# ADC_Chip.net
KiCad netlist of a schematic drawn in Altium Designer
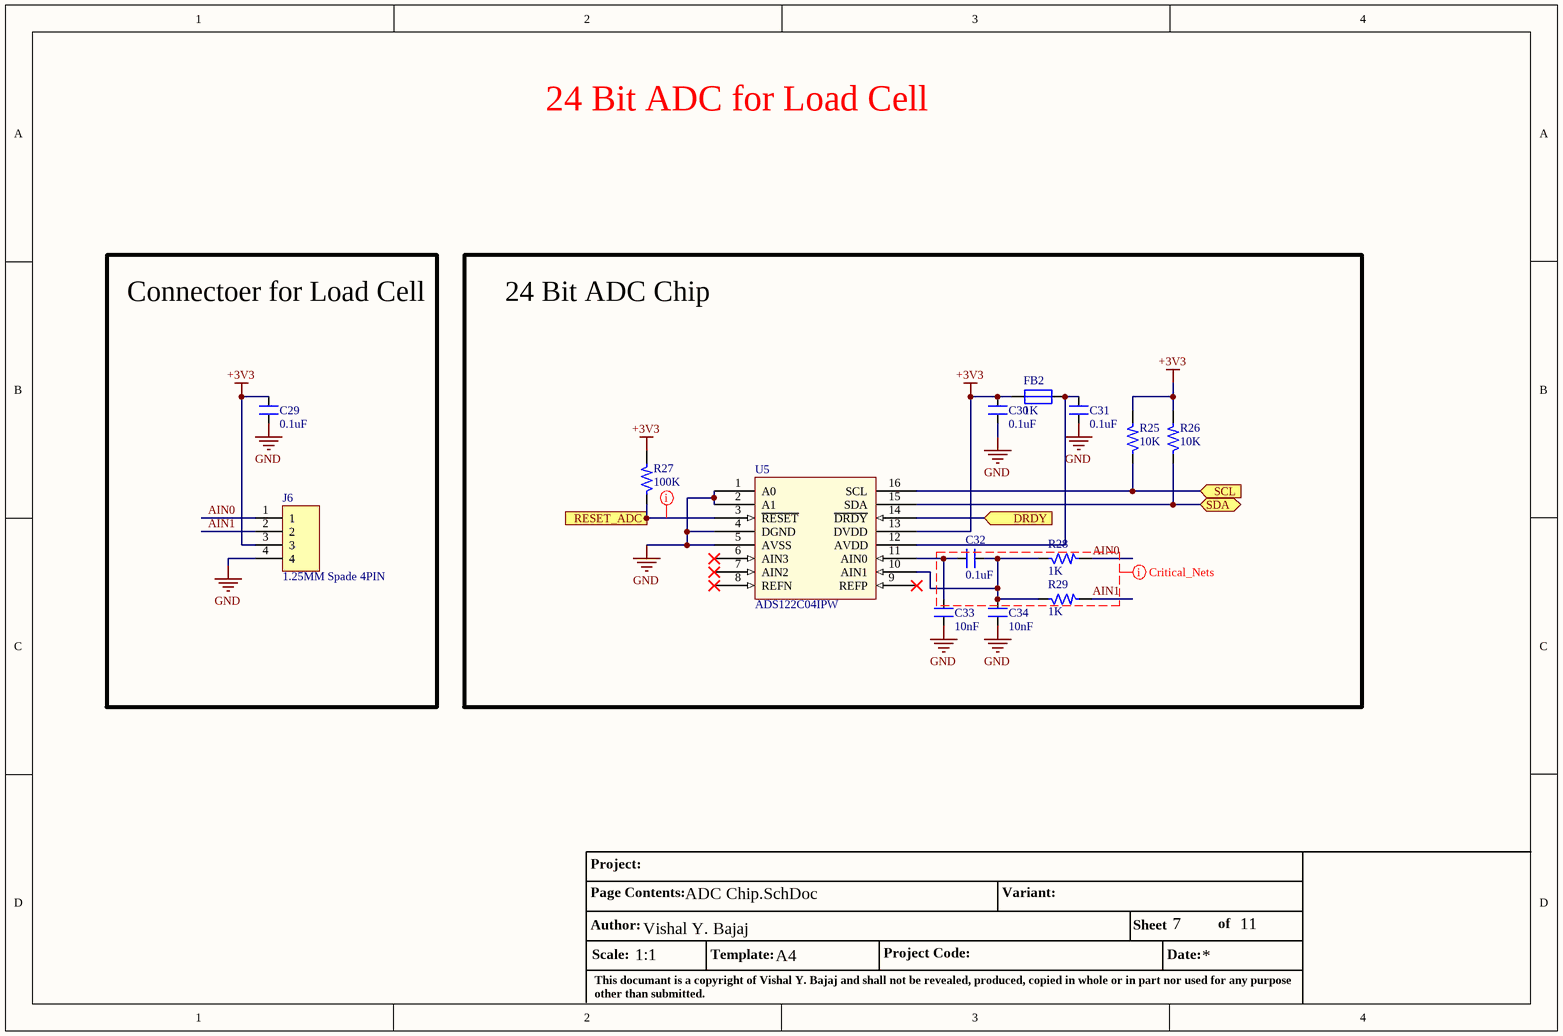
[diagram p0: ADC Chip.SchDoc]

(export (version "E")
  (design (tool "Eeschema 10.0.6"))
  (components
    (comp (ref "C29")
      (value "0.1uF")
      (footprint "CAP_0805")
      (description "0.1µF ±10% 50V Ceramic Capacitor X7R 0805 (2012 Metric)")
      (fields
        (field (name "MANUFACTURER") "Samsung")
        (field (name "MANUFACTURER PART NUMBER") "CL21B104KBCNNNC")
      )
      (libsource (lib "ESTEEMPCBLIB") (part "CAP_0.1uF-50V-10%-0805"))
    )
    (comp (ref "C30")
      (value "0.1uF")
      (footprint "CAP_0805")
      (description "0.1µF ±10% 50V Ceramic Capacitor X7R 0805 (2012 Metric)")
      (fields
        (field (name "MANUFACTURER") "Samsung")
        (field (name "MANUFACTURER PART NUMBER") "CL21B104KBCNNNC")
      )
      (libsource (lib "ESTEEMPCBLIB") (part "CAP_0.1uF-50V-10%-0805"))
    )
    (comp (ref "C31")
      (value "0.1uF")
      (footprint "CAP_0805")
      (description "0.1µF ±10% 50V Ceramic Capacitor X7R 0805 (2012 Metric)")
      (fields
        (field (name "MANUFACTURER") "Samsung")
        (field (name "MANUFACTURER PART NUMBER") "CL21B104KBCNNNC")
      )
      (libsource (lib "ESTEEMPCBLIB") (part "CAP_0.1uF-50V-10%-0805"))
    )
    (comp (ref "C32")
      (value "0.1uF")
      (footprint "CAP_0805")
      (description "0.1µF ±10% 50V Ceramic Capacitor X7R 0805 (2012 Metric)")
      (fields
        (field (name "MANUFACTURER") "Samsung")
        (field (name "MANUFACTURER PART NUMBER") "CL21B104KBCNNNC")
      )
      (libsource (lib "ESTEEMPCBLIB") (part "CAP_0.1uF-50V-10%-0805"))
    )
    (comp (ref "C33")
      (value "10nF")
      (footprint "CAP_0805")
      (description "10000pF ±10% 50V Ceramic Capacitor X7R 0805 (2012 Metric)")
      (fields
        (field (name "MANUFACTURER") "Samsung")
        (field (name "MANUFACTURER PART NUMBER") "C0805C103K5RECAUTO")
      )
      (libsource (lib "ESTEEMPCBLIB") (part "CAP_10nF-50V-10%-0805"))
    )
    (comp (ref "C34")
      (value "10nF")
      (footprint "CAP_0805")
      (description "10000pF ±10% 50V Ceramic Capacitor X7R 0805 (2012 Metric)")
      (fields
        (field (name "MANUFACTURER") "Samsung")
        (field (name "MANUFACTURER PART NUMBER") "C0805C103K5RECAUTO")
      )
      (libsource (lib "ESTEEMPCBLIB") (part "CAP_10nF-50V-10%-0805"))
    )
    (comp (ref "FB2")
      (value "1K")
      (footprint "IND_0805")
      (description "1 kOhms @ 100MHz 1 Power Line Ferrite Bead 0805 (2012 Metric) 1.6A")
      (fields
        (field (name "MANUFACTURER") "Laird")
        (field (name "MANUFACTURER PART NUMBER") "BLM21SP102SH1D")
      )
      (libsource (lib "ESTEEMPCBLIB") (part "FB_1K-100MHZ-1.6A-0805"))
    )
    (comp (ref "J6")
      (value "1.25MM Spade 4PIN")
      (footprint "CON4_50_653004117322_TH_RA")
      (description "4 Pins, 1 Row 1.25mm Pitch, right angle Connector, male")
      (fields (field (name "MANUFACTURER PART NUMBER") "653004117322") (field (name "MANUFACTURER") "JST"))
      (libsource (lib "ESTEEMPCBLIB") (part "CON-PLG_4X1-50-RA-TH"))
    )
    (comp (ref "R25")
      (value "10K")
      (footprint "RES_0603")
      (description "10 kOhms ±1% 0.1W, 1/10W Chip Resistor 0603 (1608 Metric) Automotive AEC-Q200 Thick Film")
      (fields (field (name "MANUFACTURER") "Walsin") (field (name "MANUFACTURER PART NUMBER") "WR06X1002FTL"))
      (libsource (lib "ESTEEMPCBLIB") (part "RES_10K-0.1W-1%-0603"))
    )
    (comp (ref "R26")
      (value "10K")
      (footprint "RES_0603")
      (description "10 kOhms ±1% 0.1W, 1/10W Chip Resistor 0603 (1608 Metric) Automotive AEC-Q200 Thick Film")
      (fields (field (name "MANUFACTURER") "Walsin") (field (name "MANUFACTURER PART NUMBER") "WR06X1002FTL"))
      (libsource (lib "ESTEEMPCBLIB") (part "RES_10K-0.1W-1%-0603"))
    )
    (comp (ref "R27")
      (value "100K")
      (footprint "RES_0603")
      (description "100 kOhms ±1% 0.1W, 1/10W Chip Resistor 0603 (1608 Metric) Automotive AEC-Q200 Thick Film")
      (fields
        (field (name "MANUFACTURER") "Stackpole Electronics")
        (field (name "MANUFACTURER PART NUMBER") "RMCF0603FT100K")
      )
      (libsource (lib "ESTEEMPCBLIB") (part "RES_100K-0.1W-1%-0603"))
    )
    (comp (ref "R28")
      (value "1K")
      (footprint "RES_0603")
      (description "1 kOhms ±1% 0.1W, 1/10W Chip Resistor 0603 (1608 Metric) Automotive AEC-Q200 Thick Film")
      (fields (field (name "MANUFACTURER") "Walsin") (field (name "MANUFACTURER PART NUMBER") "WR06X1001FTL"))
      (libsource (lib "ESTEEMPCBLIB") (part "RES_1K-0.1W-1%-0603"))
    )
    (comp (ref "R29")
      (value "1K")
      (footprint "RES_0603")
      (description "1 kOhms ±1% 0.1W, 1/10W Chip Resistor 0603 (1608 Metric) Automotive AEC-Q200 Thick Film")
      (fields (field (name "MANUFACTURER") "Walsin") (field (name "MANUFACTURER PART NUMBER") "WR06X1001FTL"))
      (libsource (lib "ESTEEMPCBLIB") (part "RES_1K-0.1W-1%-0603"))
    )
    (comp (ref "U5")
      (value "ADS122C04IPW")
      (footprint "TSSOP16_25-59_294_54X14_SMT")
      (description "24 Bit Analog to Digital Converter 4 Input 1 Sigma-Delta 16-TSSOP")
      (fields (field (name "MANUFACTURER") "Texas Instruments"))
      (libsource (lib "ESTEEMPCBLIB") (part "IC_ADS122C04IPW"))
    )
  )
  (nets
    (net (code "1") (name "+3V3") (class "Default")
      (node (ref "C29") (pin "2") (pinfunction "2_2") (pintype "passive"))
      (node (ref "C30") (pin "2") (pinfunction "2_2") (pintype "passive"))
      (node (ref "FB2") (pin "1") (pinfunction "1_1") (pintype "passive"))
      (node (ref "J6") (pin "3") (pinfunction "3_3") (pintype "passive"))
      (node (ref "R25") (pin "2") (pinfunction "2_2") (pintype "passive"))
      (node (ref "R26") (pin "2") (pinfunction "2_2") (pintype "passive"))
      (node (ref "R27") (pin "2") (pinfunction "2_2") (pintype "passive"))
      (node (ref "U5") (pin "13") (pinfunction "DVDD_13") (pintype "power_in"))
    )
    (net (code "2") (name "/AIN0") (class "Default")
      (node (ref "J6") (pin "1") (pinfunction "1_1") (pintype "passive"))
      (node (ref "R28") (pin "2") (pinfunction "2_2") (pintype "passive"))
    )
    (net (code "3") (name "/AIN1") (class "Default")
      (node (ref "J6") (pin "2") (pinfunction "2_2") (pintype "passive"))
      (node (ref "R29") (pin "2") (pinfunction "2_2") (pintype "passive"))
    )
    (net (code "4") (name "/DRDY") (class "Default")
      (node (ref "U5") (pin "14") (pinfunction "DRDY_14") (pintype "input"))
    )
    (net (code "5") (name "/RESET_ADC") (class "Default")
      (node (ref "R27") (pin "1") (pinfunction "1_1") (pintype "passive"))
      (node (ref "U5") (pin "3") (pinfunction "RESET_3") (pintype "input"))
    )
    (net (code "6") (name "/SCL") (class "Default")
      (node (ref "R25") (pin "1") (pinfunction "1_1") (pintype "passive"))
      (node (ref "U5") (pin "16") (pinfunction "SCL_16") (pintype "open_collector"))
    )
    (net (code "7") (name "/SDA") (class "Default")
      (node (ref "R26") (pin "1") (pinfunction "1_1") (pintype "passive"))
      (node (ref "U5") (pin "15") (pinfunction "SDA_15") (pintype "open_collector"))
    )
    (net (code "8") (name "GND") (class "Default")
      (node (ref "C29") (pin "1") (pinfunction "1_1") (pintype "passive"))
      (node (ref "C30") (pin "1") (pinfunction "1_1") (pintype "passive"))
      (node (ref "C31") (pin "1") (pinfunction "1_1") (pintype "passive"))
      (node (ref "C33") (pin "1") (pinfunction "1_1") (pintype "passive"))
      (node (ref "C34") (pin "1") (pinfunction "1_1") (pintype "passive"))
      (node (ref "J6") (pin "4") (pinfunction "4_4") (pintype "passive"))
      (node (ref "U5") (pin "1") (pinfunction "A0_1") (pintype "passive"))
      (node (ref "U5") (pin "2") (pinfunction "A1_2") (pintype "passive"))
      (node (ref "U5") (pin "4") (pinfunction "DGND_4") (pintype "power_in"))
      (node (ref "U5") (pin "5") (pinfunction "AVSS_5") (pintype "power_in"))
    )
    (net (code "9") (name "Net-(U5-AIN0)") (class "Default")
      (node (ref "C32") (pin "1") (pinfunction "1_1") (pintype "passive"))
      (node (ref "C33") (pin "2") (pinfunction "2_2") (pintype "passive"))
      (node (ref "U5") (pin "11") (pinfunction "AIN0_11") (pintype "input"))
    )
    (net (code "10") (name "Net-(U5-AIN1)") (class "Default")
      (node (ref "C32") (pin "2") (pinfunction "2_2") (pintype "passive"))
      (node (ref "C34") (pin "2") (pinfunction "2_2") (pintype "passive"))
      (node (ref "R28") (pin "1") (pinfunction "1_1") (pintype "passive"))
      (node (ref "R29") (pin "1") (pinfunction "1_1") (pintype "passive"))
      (node (ref "U5") (pin "10") (pinfunction "AIN1_10") (pintype "input"))
    )
    (net (code "11") (name "Net-(U5-AVDD)") (class "Default")
      (node (ref "C31") (pin "2") (pinfunction "2_2") (pintype "passive"))
      (node (ref "FB2") (pin "2") (pinfunction "2_2") (pintype "passive"))
      (node (ref "U5") (pin "12") (pinfunction "AVDD_12") (pintype "power_in"))
    )
    (net (code "12") (name "unconnected-(U5-AIN2-Pad7)") (class "Default")
      (node (ref "U5") (pin "7") (pinfunction "AIN2_7") (pintype "input+no_connect"))
    )
    (net (code "13") (name "unconnected-(U5-AIN3-Pad6)") (class "Default")
      (node (ref "U5") (pin "6") (pinfunction "AIN3_6") (pintype "input+no_connect"))
    )
    (net (code "14") (name "unconnected-(U5-REFN-Pad8)") (class "Default")
      (node (ref "U5") (pin "8") (pinfunction "REFN_8") (pintype "input+no_connect"))
    )
    (net (code "15") (name "unconnected-(U5-REFP-Pad9)") (class "Default")
      (node (ref "U5") (pin "9") (pinfunction "REFP_9") (pintype "input+no_connect"))
    )
  )
)
